# GRLV_double_30v_v0_3.net
KiCad netlist of a schematic drawn in Altium Designer
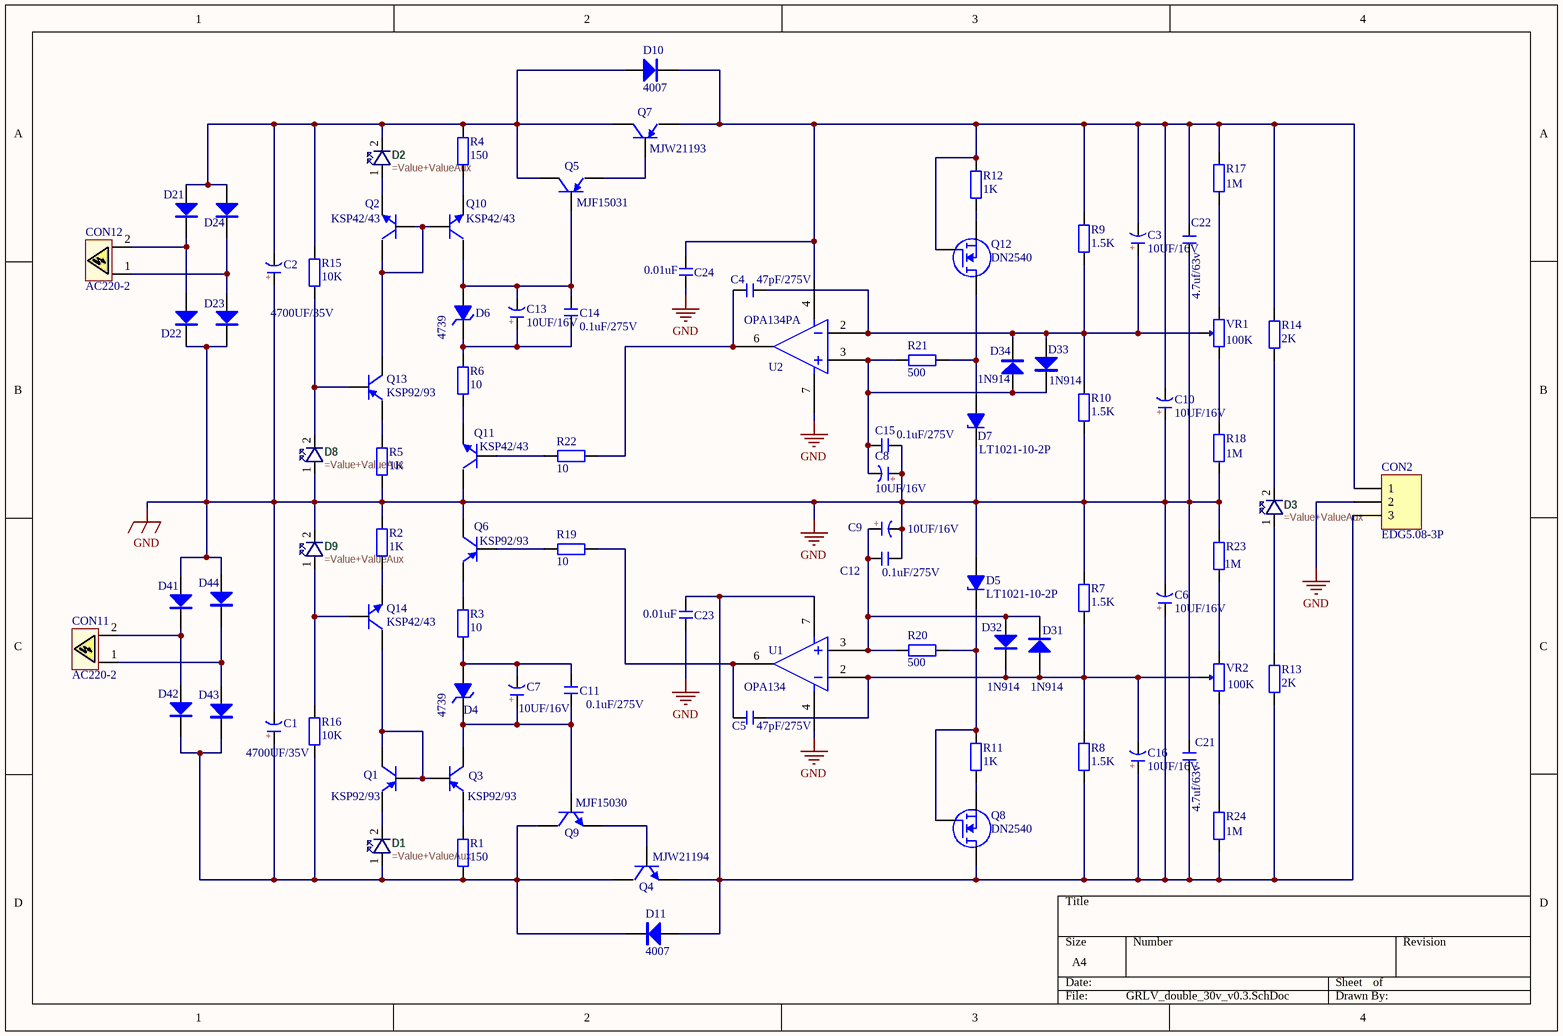
[diagram p0: GRLV_double_30v_v0.3.SchDoc]

(export (version "E")
  (design (tool "Eeschema 10.0.6"))
  (components
    (comp (ref "C1")
      (value "4700UF/35V")
      (footprint "CAP 10*22*31.5")
      (description "直插电解电容")
      (fields (field (name "版权归属") "源创客"))
      (libsource (lib "电阻-电容-电感") (part "C-CAP"))
    )
    (comp (ref "C2")
      (value "4700UF/35V")
      (footprint "CAP 10*22*31.5")
      (description "直插电解电容")
      (fields (field (name "版权归属") "源创客"))
      (libsource (lib "电阻-电容-电感") (part "C-CAP"))
    )
    (comp (ref "C3")
      (value "10UF/16V")
      (footprint "CAP 2.5*6.3*7")
      (description "直插电解电容")
      (fields (field (name "版权归属") "源创客"))
      (libsource (lib "电阻-电容-电感") (part "C-CAP"))
    )
    (comp (ref "C4")
      (value "47pF/275V")
      (footprint "CBB 6.3*6.3*5")
      (description "CBB电容")
      (fields (field (name "版权归属") "源创客"))
      (libsource (lib "电阻-电容-电感") (part "C-CBB"))
    )
    (comp (ref "C5")
      (value "47pF/275V")
      (footprint "CBB 6.3*6.3*5")
      (description "CBB电容")
      (fields (field (name "版权归属") "源创客"))
      (libsource (lib "电阻-电容-电感") (part "C-CBB"))
    )
    (comp (ref "C6")
      (value "10UF/16V")
      (footprint "CAP 3.5*8*11.5")
      (description "直插电解电容")
      (fields (field (name "版权归属") "源创客"))
      (libsource (lib "电阻-电容-电感") (part "C-CAP"))
    )
    (comp (ref "C7")
      (value "10UF/16V")
      (footprint "CAP 2.5*6.3*11.2")
      (description "直插电解电容")
      (fields (field (name "版权归属") "源创客"))
      (libsource (lib "电阻-电容-电感") (part "C-CAP"))
    )
    (comp (ref "C8")
      (value "10UF/16V")
      (footprint "CAP 2.5*6.3*7")
      (description "直插电解电容")
      (fields (field (name "版权归属") "源创客"))
      (libsource (lib "") (part "C-CAP_1"))
    )
    (comp (ref "C9")
      (value "10UF/16V")
      (footprint "CAP 2.5*6.3*7")
      (description "直插电解电容")
      (fields (field (name "版权归属") "源创客"))
      (libsource (lib "") (part "C-CAP_1"))
    )
    (comp (ref "C10")
      (value "10UF/16V")
      (footprint "CAP 3.5*8*11.5")
      (description "直插电解电容")
      (fields (field (name "版权归属") "源创客"))
      (libsource (lib "电阻-电容-电感") (part "C-CAP"))
    )
    (comp (ref "C11")
      (value "0.1uF/275V")
      (footprint "CBB 6.3*6.3*5")
      (description "CBB电容")
      (fields (field (name "版权归属") "源创客"))
      (libsource (lib "电阻-电容-电感") (part "C-CBB"))
    )
    (comp (ref "C12")
      (value "0.1uF/275V")
      (footprint "CBB 6.3*6.3*5")
      (description "CBB电容")
      (fields (field (name "版权归属") "源创客"))
      (libsource (lib "电阻-电容-电感") (part "C-CBB"))
    )
    (comp (ref "C13")
      (value "10UF/16V")
      (footprint "CAP 2.5*6.3*11.2")
      (description "直插电解电容")
      (fields (field (name "版权归属") "源创客"))
      (libsource (lib "电阻-电容-电感") (part "C-CAP"))
    )
    (comp (ref "C14")
      (value "0.1uF/275V")
      (footprint "CBB 6.3*6.3*5")
      (description "CBB电容")
      (fields (field (name "版权归属") "源创客"))
      (libsource (lib "电阻-电容-电感") (part "C-CBB"))
    )
    (comp (ref "C15")
      (value "0.1uF/275V")
      (footprint "CBB 6.3*6.3*5")
      (description "CBB电容")
      (fields (field (name "版权归属") "源创客"))
      (libsource (lib "电阻-电容-电感") (part "C-CBB"))
    )
    (comp (ref "C16")
      (value "10UF/16V")
      (footprint "CAP 2.5*6.3*7")
      (description "直插电解电容")
      (fields (field (name "版权归属") "源创客"))
      (libsource (lib "电阻-电容-电感") (part "C-CAP"))
    )
    (comp (ref "C21")
      (value "4.7uf/63v")
      (footprint "CBB 7.2*7.2*13")
      (description "MKS薄膜电容")
      (libsource (lib "电阻-电容-电感") (part "C-MKS"))
    )
    (comp (ref "C22")
      (value "4.7uf/63v")
      (footprint "CBB 7.2*7.2*13")
      (description "MKS薄膜电容")
      (libsource (lib "电阻-电容-电感") (part "C-MKS"))
    )
    (comp (ref "C23")
      (value "0.01uF")
      (footprint "CBB 6.3*6.3*5")
      (description "CBB电容")
      (fields (field (name "Comment") "0.01uF/275V") (field (name "版权归属") "源创客"))
      (libsource (lib "电阻-电容-电感") (part "C-CBB"))
    )
    (comp (ref "C24")
      (value "0.01uF")
      (footprint "CBB 6.3*6.3*5")
      (description "CBB电容")
      (fields (field (name "Comment") "0.01uF/275V") (field (name "版权归属") "源创客"))
      (libsource (lib "电阻-电容-电感") (part "C-CBB"))
    )
    (comp (ref "CON2")
      (value "EDG5.08-3P")
      (footprint "HX5.08-3S")
      (libsource (lib "Connectors") (part "EDG5.08-3P"))
    )
    (comp (ref "CON11")
      (value "AC220-2")
      (footprint "HX5.08-2L")
      (libsource (lib "Connectors") (part "AC220-2"))
    )
    (comp (ref "CON12")
      (value "AC220-2")
      (footprint "HX5.08-2L")
      (libsource (lib "Connectors") (part "AC220-2"))
    )
    (comp (ref "D1")
      (value "~")
      (footprint "LED 3MM-R")
      (description "直插式LED")
      (libsource (lib "LED") (part "LED"))
    )
    (comp (ref "D2")
      (value "~")
      (footprint "LED 3MM-R")
      (description "直插式LED")
      (libsource (lib "LED") (part "LED"))
    )
    (comp (ref "D3")
      (value "~")
      (footprint "LED 3MM-R")
      (description "直插式LED")
      (libsource (lib "LED") (part "LED"))
    )
    (comp (ref "D4")
      (value "4739")
      (footprint "DO-41")
      (description "9.1V/1W稳压管")
      (libsource (lib "二极管-整流桥") (part "1N4739"))
    )
    (comp (ref "D5")
      (value "LT1021-10-2P")
      (footprint "DIP8-300_MH")
      (description "10V Precision Reference 2 Pin Config")
      (libsource (lib "电压参考") (part "LT1021-10-2P"))
    )
    (comp (ref "D6")
      (value "4739")
      (footprint "DO-41")
      (description "9.1V/1W稳压管")
      (libsource (lib "二极管-整流桥") (part "1N4739"))
    )
    (comp (ref "D7")
      (value "LT1021-10-2P")
      (footprint "DIP8-300_MH")
      (description "10V Precision Reference 2 Pin Config")
      (libsource (lib "电压参考") (part "LT1021-10-2P"))
    )
    (comp (ref "D8")
      (value "~")
      (footprint "LED 3MM-R")
      (description "直插式LED")
      (libsource (lib "LED") (part "LED"))
    )
    (comp (ref "D9")
      (value "~")
      (footprint "LED 3MM-R")
      (description "直插式LED")
      (libsource (lib "LED") (part "LED"))
    )
    (comp (ref "D10")
      (value "4007")
      (footprint "DO-41")
      (description "整流二极管")
      (fields (field (name "版权归属") "源创客"))
      (libsource (lib "二极管-整流桥") (part "1N4007"))
    )
    (comp (ref "D11")
      (value "4007")
      (footprint "DO-41")
      (description "整流二极管")
      (fields (field (name "版权归属") "源创客"))
      (libsource (lib "二极管-整流桥") (part "1N4007"))
    )
    (comp (ref "D21")
      (value "VS-HFA08TB60-M3")
      (footprint "TO220AC")
      (description "Ultrafast Soft Recovery Diado 8A 600V")
      (libsource (lib "二极管-整流桥") (part "VS-HFA08TB60-M3"))
    )
    (comp (ref "D22")
      (value "VS-HFA08TB60-M3")
      (footprint "TO220AC")
      (description "Ultrafast Soft Recovery Diado 8A 600V")
      (libsource (lib "二极管-整流桥") (part "VS-HFA08TB60-M3"))
    )
    (comp (ref "D23")
      (value "VS-HFA08TB60-M3")
      (footprint "TO220AC")
      (description "Ultrafast Soft Recovery Diado 8A 600V")
      (libsource (lib "二极管-整流桥") (part "VS-HFA08TB60-M3"))
    )
    (comp (ref "D24")
      (value "VS-HFA08TB60-M3")
      (footprint "TO220AC")
      (description "Ultrafast Soft Recovery Diado 8A 600V")
      (libsource (lib "二极管-整流桥") (part "VS-HFA08TB60-M3"))
    )
    (comp (ref "D31")
      (value "1N914")
      (footprint "DO-35")
      (description "高速开关管 1V/0.25W")
      (libsource (lib "二极管-整流桥") (part "1N914"))
    )
    (comp (ref "D32")
      (value "1N914")
      (footprint "DO-35")
      (description "高速开关管 1V/0.25W")
      (libsource (lib "二极管-整流桥") (part "1N914"))
    )
    (comp (ref "D33")
      (value "1N914")
      (footprint "DO-35")
      (description "高速开关管 1V/0.25W")
      (libsource (lib "二极管-整流桥") (part "1N914"))
    )
    (comp (ref "D34")
      (value "1N914")
      (footprint "DO-35")
      (description "高速开关管 1V/0.25W")
      (libsource (lib "二极管-整流桥") (part "1N914"))
    )
    (comp (ref "D41")
      (value "VS-HFA08TB60-M3")
      (footprint "TO220AC")
      (description "Ultrafast Soft Recovery Diado 8A 600V")
      (libsource (lib "二极管-整流桥") (part "VS-HFA08TB60-M3"))
    )
    (comp (ref "D42")
      (value "VS-HFA08TB60-M3")
      (footprint "TO220AC")
      (description "Ultrafast Soft Recovery Diado 8A 600V")
      (libsource (lib "二极管-整流桥") (part "VS-HFA08TB60-M3"))
    )
    (comp (ref "D43")
      (value "VS-HFA08TB60-M3")
      (footprint "TO220AC")
      (description "Ultrafast Soft Recovery Diado 8A 600V")
      (libsource (lib "二极管-整流桥") (part "VS-HFA08TB60-M3"))
    )
    (comp (ref "D44")
      (value "VS-HFA08TB60-M3")
      (footprint "TO220AC")
      (description "Ultrafast Soft Recovery Diado 8A 600V")
      (libsource (lib "二极管-整流桥") (part "VS-HFA08TB60-M3"))
    )
    (comp (ref "Q1")
      (value "KSP92/93")
      (footprint "TO92A")
      (description "High Voltage PNP Transistor")
      (libsource (lib "三极管") (part "KSP92/93"))
    )
    (comp (ref "Q2")
      (value "KSP42/43")
      (footprint "TO92A")
      (description "High Voltage NPN Transistor")
      (libsource (lib "三极管") (part "KSP42/43"))
    )
    (comp (ref "Q3")
      (value "KSP92/93")
      (footprint "TO92A")
      (description "High Voltage PNP Transistor")
      (libsource (lib "三极管") (part "KSP92/93"))
    )
    (comp (ref "Q4")
      (value "MJW21194")
      (footprint "TO247V")
      (description "Power NPN Transistor")
      (libsource (lib "三极管") (part "MJW21194"))
    )
    (comp (ref "Q5")
      (value "MJF15031")
      (footprint "TO220V")
      (description "Power PNP Transistor")
      (libsource (lib "三极管") (part "MJF15031"))
    )
    (comp (ref "Q6")
      (value "KSP92/93")
      (footprint "TO92A")
      (description "High Voltage PNP Transistor")
      (libsource (lib "三极管") (part "KSP92/93"))
    )
    (comp (ref "Q7")
      (value "MJW21193")
      (footprint "TO247V")
      (description "Power PNP Transistor")
      (libsource (lib "三极管") (part "MJW21193"))
    )
    (comp (ref "Q8")
      (value "DN2540")
      (footprint "TO92A")
      (description "N沟道耗尽型DMOS场效应管 400V/150ma")
      (libsource (lib "场效应管") (part "DN2540"))
    )
    (comp (ref "Q9")
      (value "MJF15030")
      (footprint "TO220V")
      (description "Power NPN Transistor")
      (libsource (lib "三极管") (part "MJF15030"))
    )
    (comp (ref "Q10")
      (value "KSP42/43")
      (footprint "TO92A")
      (description "High Voltage NPN Transistor")
      (libsource (lib "三极管") (part "KSP42/43"))
    )
    (comp (ref "Q11")
      (value "KSP42/43")
      (footprint "TO92A")
      (description "High Voltage NPN Transistor")
      (libsource (lib "三极管") (part "KSP42/43"))
    )
    (comp (ref "Q12")
      (value "DN2540")
      (footprint "TO92A")
      (description "N沟道耗尽型DMOS场效应管 400V/150ma")
      (libsource (lib "场效应管") (part "DN2540"))
    )
    (comp (ref "Q13")
      (value "KSP92/93")
      (footprint "TO92A")
      (description "High Voltage PNP Transistor")
      (libsource (lib "三极管") (part "KSP92/93"))
    )
    (comp (ref "Q14")
      (value "KSP42/43")
      (footprint "TO92A")
      (description "High Voltage NPN Transistor")
      (libsource (lib "三极管") (part "KSP42/43"))
    )
    (comp (ref "R1")
      (value "150")
      (footprint "RS 1/4W")
      (description "直插色环电阻")
      (fields (field (name "版权归属") "源创客"))
      (libsource (lib "电阻-电容-电感") (part "R-CRR"))
    )
    (comp (ref "R2")
      (value "1K")
      (footprint "RS 1/4W")
      (description "直插色环电阻")
      (fields (field (name "版权归属") "源创客"))
      (libsource (lib "电阻-电容-电感") (part "R-CRR"))
    )
    (comp (ref "R3")
      (value "10")
      (footprint "RS 1/4W")
      (description "直插色环电阻")
      (fields (field (name "版权归属") "源创客"))
      (libsource (lib "电阻-电容-电感") (part "R-CRR"))
    )
    (comp (ref "R4")
      (value "150")
      (footprint "RS 1/4W")
      (description "直插色环电阻")
      (fields (field (name "版权归属") "源创客"))
      (libsource (lib "电阻-电容-电感") (part "R-CRR"))
    )
    (comp (ref "R5")
      (value "1K")
      (footprint "RS 1/4W")
      (description "直插色环电阻")
      (fields (field (name "版权归属") "源创客"))
      (libsource (lib "电阻-电容-电感") (part "R-CRR"))
    )
    (comp (ref "R6")
      (value "10")
      (footprint "RS 1/4W")
      (description "直插色环电阻")
      (fields (field (name "版权归属") "源创客"))
      (libsource (lib "电阻-电容-电感") (part "R-CRR"))
    )
    (comp (ref "R7")
      (value "1.5K")
      (footprint "RS 1/4W")
      (description "直插色环电阻")
      (fields (field (name "版权归属") "源创客"))
      (libsource (lib "电阻-电容-电感") (part "R-CRR"))
    )
    (comp (ref "R8")
      (value "1.5K")
      (footprint "RS 1/4W")
      (description "直插色环电阻")
      (fields (field (name "版权归属") "源创客"))
      (libsource (lib "电阻-电容-电感") (part "R-CRR"))
    )
    (comp (ref "R9")
      (value "1.5K")
      (footprint "RS 1/4W")
      (description "直插色环电阻")
      (fields (field (name "版权归属") "源创客"))
      (libsource (lib "电阻-电容-电感") (part "R-CRR"))
    )
    (comp (ref "R10")
      (value "1.5K")
      (footprint "RS 1/4W")
      (description "直插色环电阻")
      (fields (field (name "版权归属") "源创客"))
      (libsource (lib "电阻-电容-电感") (part "R-CRR"))
    )
    (comp (ref "R11")
      (value "1K")
      (footprint "RS 1/4W")
      (description "直插色环电阻")
      (fields (field (name "版权归属") "源创客"))
      (libsource (lib "电阻-电容-电感") (part "R-CRR"))
    )
    (comp (ref "R12")
      (value "1K")
      (footprint "RS 1/4W")
      (description "直插色环电阻")
      (fields (field (name "版权归属") "源创客"))
      (libsource (lib "电阻-电容-电感") (part "R-CRR"))
    )
    (comp (ref "R13")
      (value "2K")
      (footprint "RS 1/4W")
      (description "直插色环电阻")
      (fields (field (name "版权归属") "源创客"))
      (libsource (lib "电阻-电容-电感") (part "R-CRR"))
    )
    (comp (ref "R14")
      (value "2K")
      (footprint "RS 1/4W")
      (description "直插色环电阻")
      (fields (field (name "版权归属") "源创客"))
      (libsource (lib "电阻-电容-电感") (part "R-CRR"))
    )
    (comp (ref "R15")
      (value "10K")
      (footprint "RS 1/4W")
      (description "直插色环电阻")
      (fields (field (name "版权归属") "源创客"))
      (libsource (lib "电阻-电容-电感") (part "R-CRR"))
    )
    (comp (ref "R16")
      (value "10K")
      (footprint "RS 1/4W")
      (description "直插色环电阻")
      (fields (field (name "版权归属") "源创客"))
      (libsource (lib "电阻-电容-电感") (part "R-CRR"))
    )
    (comp (ref "R17")
      (value "1M")
      (footprint "RS 1/4W")
      (description "直插色环电阻")
      (fields (field (name "版权归属") "源创客"))
      (libsource (lib "电阻-电容-电感") (part "R-CRR"))
    )
    (comp (ref "R18")
      (value "1M")
      (footprint "RS 1/4W")
      (description "直插色环电阻")
      (fields (field (name "版权归属") "源创客"))
      (libsource (lib "电阻-电容-电感") (part "R-CRR"))
    )
    (comp (ref "R19")
      (value "10")
      (footprint "RS 1/4W")
      (description "直插色环电阻")
      (fields (field (name "版权归属") "源创客"))
      (libsource (lib "电阻-电容-电感") (part "R-CRR"))
    )
    (comp (ref "R20")
      (value "500")
      (footprint "RS 1/4W")
      (description "直插色环电阻")
      (fields (field (name "版权归属") "源创客"))
      (libsource (lib "电阻-电容-电感") (part "R-CRR"))
    )
    (comp (ref "R21")
      (value "500")
      (footprint "RS 1/4W")
      (description "直插色环电阻")
      (fields (field (name "版权归属") "源创客"))
      (libsource (lib "电阻-电容-电感") (part "R-CRR"))
    )
    (comp (ref "R22")
      (value "10")
      (footprint "RS 1/4W")
      (description "直插色环电阻")
      (fields (field (name "版权归属") "源创客"))
      (libsource (lib "电阻-电容-电感") (part "R-CRR"))
    )
    (comp (ref "R23")
      (value "1M")
      (footprint "RS 1/4W")
      (description "直插色环电阻")
      (fields (field (name "版权归属") "源创客"))
      (libsource (lib "电阻-电容-电感") (part "R-CRR"))
    )
    (comp (ref "R24")
      (value "1M")
      (footprint "RS 1/4W")
      (description "直插色环电阻")
      (fields (field (name "版权归属") "源创客"))
      (libsource (lib "电阻-电容-电感") (part "R-CRR"))
    )
    (comp (ref "U1") (value "OPA134") (footprint "DIP8-300_MH") (libsource (lib "运放") (part "OPA134PA")))
    (comp (ref "U2") (value "OPA134PA") (footprint "DIP8-300_MH") (libsource (lib "运放") (part "OPA134PA")))
    (comp (ref "VR1")
      (value "100K")
      (footprint "RS 1/2W-VR")
      (description "直插可调电阻-顶调")
      (fields (field (name "Comment") "VR-W"))
      (libsource (lib "电阻-电容-电感") (part "VR-W"))
    )
    (comp (ref "VR2")
      (value "100K")
      (footprint "RS 1/2W-VR")
      (description "直插可调电阻-顶调")
      (fields (field (name "Comment") "VR-W"))
      (libsource (lib "电阻-电容-电感") (part "VR-W"))
    )
  )
  (nets
    (net (code "1") (name "GND") (class "Default")
      (node (ref "C1") (pin "2") (pinfunction "K_2") (pintype "passive"))
      (node (ref "C10") (pin "1") (pinfunction "A_1") (pintype "passive"))
      (node (ref "C12") (pin "2") (pinfunction "2_2") (pintype "passive"))
      (node (ref "C15") (pin "2") (pinfunction "2_2") (pintype "passive"))
      (node (ref "C2") (pin "1") (pinfunction "A_1") (pintype "passive"))
      (node (ref "C21") (pin "2") (pinfunction "2_2") (pintype "passive"))
      (node (ref "C22") (pin "1") (pinfunction "1_1") (pintype "passive"))
      (node (ref "C23") (pin "1") (pinfunction "1_1") (pintype "passive"))
      (node (ref "C24") (pin "1") (pinfunction "1_1") (pintype "passive"))
      (node (ref "C6") (pin "2") (pinfunction "K_2") (pintype "passive"))
      (node (ref "C8") (pin "1") (pinfunction "A_1") (pintype "passive"))
      (node (ref "C9") (pin "2") (pinfunction "K_2") (pintype "passive"))
      (node (ref "CON2") (pin "2") (pinfunction "2_2") (pintype "passive"))
      (node (ref "D22") (pin "1") (pinfunction "Cathode_1") (pintype "passive"))
      (node (ref "D23") (pin "1") (pinfunction "Cathode_1") (pintype "passive"))
      (node (ref "D41") (pin "2") (pinfunction "Anode_2") (pintype "passive"))
      (node (ref "D44") (pin "2") (pinfunction "Anode_2") (pintype "passive"))
      (node (ref "D5") (pin "4") (pinfunction "A_4") (pintype "passive"))
      (node (ref "D7") (pin "6") (pinfunction "K_6") (pintype "passive"))
      (node (ref "D8") (pin "1") (pinfunction "A_1") (pintype "passive"))
      (node (ref "D9") (pin "2") (pinfunction "K_2") (pintype "passive"))
      (node (ref "Q11") (pin "3") (pinfunction "C_3") (pintype "passive"))
      (node (ref "Q6") (pin "3") (pinfunction "C_3") (pintype "passive"))
      (node (ref "R10") (pin "1") (pinfunction "1_1") (pintype "passive"))
      (node (ref "R18") (pin "1") (pinfunction "1_1") (pintype "passive"))
      (node (ref "R2") (pin "2") (pinfunction "2_2") (pintype "passive"))
      (node (ref "R23") (pin "2") (pinfunction "2_2") (pintype "passive"))
      (node (ref "R5") (pin "1") (pinfunction "1_1") (pintype "passive"))
      (node (ref "R7") (pin "2") (pinfunction "2_2") (pintype "passive"))
      (node (ref "U1") (pin "4") (pinfunction "V-_4") (pintype "passive"))
      (node (ref "U2") (pin "7") (pinfunction "V+_7") (pintype "passive"))
    )
    (net (code "2") (name "Net-(C1-A)") (class "Default")
      (node (ref "C1") (pin "1") (pinfunction "A_1") (pintype "passive"))
      (node (ref "D1") (pin "1") (pinfunction "A_1") (pintype "passive"))
      (node (ref "D11") (pin "2") (pinfunction "K_2") (pintype "passive"))
      (node (ref "D42") (pin "1") (pinfunction "Cathode_1") (pintype "passive"))
      (node (ref "D43") (pin "1") (pinfunction "Cathode_1") (pintype "passive"))
      (node (ref "Q4") (pin "2") (pinfunction "C_2") (pintype "passive"))
      (node (ref "Q9") (pin "2") (pinfunction "C_2") (pintype "passive"))
      (node (ref "R1") (pin "1") (pinfunction "1_1") (pintype "passive"))
      (node (ref "R16") (pin "1") (pinfunction "1_1") (pintype "passive"))
    )
    (net (code "3") (name "Net-(C2-K)") (class "Default")
      (node (ref "C2") (pin "2") (pinfunction "K_2") (pintype "passive"))
      (node (ref "D10") (pin "1") (pinfunction "A_1") (pintype "passive"))
      (node (ref "D2") (pin "2") (pinfunction "K_2") (pintype "passive"))
      (node (ref "D21") (pin "2") (pinfunction "Anode_2") (pintype "passive"))
      (node (ref "D24") (pin "2") (pinfunction "Anode_2") (pintype "passive"))
      (node (ref "Q5") (pin "2") (pinfunction "C_2") (pintype "passive"))
      (node (ref "Q7") (pin "2") (pinfunction "C_2") (pintype "passive"))
      (node (ref "R15") (pin "2") (pinfunction "2_2") (pintype "passive"))
      (node (ref "R4") (pin "2") (pinfunction "2_2") (pintype "passive"))
    )
    (net (code "4") (name "Net-(C3-A)") (class "Default")
      (node (ref "C3") (pin "1") (pinfunction "A_1") (pintype "passive"))
      (node (ref "C4") (pin "2") (pinfunction "2_2") (pintype "passive"))
      (node (ref "D33") (pin "1") (pinfunction "A_1") (pintype "passive"))
      (node (ref "D34") (pin "2") (pinfunction "K_2") (pintype "passive"))
      (node (ref "R10") (pin "2") (pinfunction "2_2") (pintype "passive"))
      (node (ref "R9") (pin "1") (pinfunction "1_1") (pintype "passive"))
      (node (ref "U2") (pin "2") (pinfunction "-in_2") (pintype "passive"))
      (node (ref "VR1") (pin "3") (pinfunction "3_3") (pintype "passive"))
    )
    (net (code "5") (name "Net-(C7-A)") (class "Default")
      (node (ref "C11") (pin "1") (pinfunction "1_1") (pintype "passive"))
      (node (ref "C7") (pin "1") (pinfunction "A_1") (pintype "passive"))
      (node (ref "D4") (pin "2") (pinfunction "K_2") (pintype "passive"))
      (node (ref "Q3") (pin "3") (pinfunction "C_3") (pintype "passive"))
      (node (ref "Q9") (pin "1") (pinfunction "B_1") (pintype "passive"))
    )
    (net (code "6") (name "Net-(C7-K)") (class "Default")
      (node (ref "C11") (pin "2") (pinfunction "2_2") (pintype "passive"))
      (node (ref "C7") (pin "2") (pinfunction "K_2") (pintype "passive"))
      (node (ref "D4") (pin "1") (pinfunction "A_1") (pintype "passive"))
      (node (ref "R3") (pin "1") (pinfunction "1_1") (pintype "passive"))
    )
    (net (code "7") (name "Net-(C8-K)") (class "Default")
      (node (ref "C15") (pin "1") (pinfunction "1_1") (pintype "passive"))
      (node (ref "C8") (pin "2") (pinfunction "K_2") (pintype "passive"))
      (node (ref "D33") (pin "2") (pinfunction "K_2") (pintype "passive"))
      (node (ref "D34") (pin "1") (pinfunction "A_1") (pintype "passive"))
      (node (ref "R21") (pin "1") (pinfunction "1_1") (pintype "passive"))
      (node (ref "U2") (pin "3") (pinfunction "+in_3") (pintype "passive"))
    )
    (net (code "8") (name "Net-(C9-A)") (class "Default")
      (node (ref "C12") (pin "1") (pinfunction "1_1") (pintype "passive"))
      (node (ref "C9") (pin "1") (pinfunction "A_1") (pintype "passive"))
      (node (ref "D31") (pin "2") (pinfunction "K_2") (pintype "passive"))
      (node (ref "D32") (pin "1") (pinfunction "A_1") (pintype "passive"))
      (node (ref "R20") (pin "1") (pinfunction "1_1") (pintype "passive"))
      (node (ref "U1") (pin "3") (pinfunction "+in_3") (pintype "passive"))
    )
    (net (code "9") (name "Net-(C10-K)") (class "Default")
      (node (ref "C10") (pin "2") (pinfunction "K_2") (pintype "passive"))
      (node (ref "C22") (pin "2") (pinfunction "2_2") (pintype "passive"))
      (node (ref "C24") (pin "2") (pinfunction "2_2") (pintype "passive"))
      (node (ref "C3") (pin "2") (pinfunction "K_2") (pintype "passive"))
      (node (ref "CON2") (pin "1") (pinfunction "1_1") (pintype "passive"))
      (node (ref "D10") (pin "2") (pinfunction "K_2") (pintype "passive"))
      (node (ref "Q12") (pin "2") (pinfunction "G_2") (pintype "passive"))
      (node (ref "Q7") (pin "3") (pinfunction "E_3") (pintype "passive"))
      (node (ref "R12") (pin "2") (pinfunction "2_2") (pintype "passive"))
      (node (ref "R14") (pin "2") (pinfunction "2_2") (pintype "passive"))
      (node (ref "R17") (pin "2") (pinfunction "2_2") (pintype "passive"))
      (node (ref "R9") (pin "2") (pinfunction "2_2") (pintype "passive"))
      (node (ref "U2") (pin "4") (pinfunction "V-_4") (pintype "passive"))
    )
    (net (code "10") (name "Net-(C13-A)") (class "Default")
      (node (ref "C13") (pin "1") (pinfunction "A_1") (pintype "passive"))
      (node (ref "C14") (pin "1") (pinfunction "1_1") (pintype "passive"))
      (node (ref "D6") (pin "2") (pinfunction "K_2") (pintype "passive"))
      (node (ref "R6") (pin "2") (pinfunction "2_2") (pintype "passive"))
    )
    (net (code "11") (name "Net-(C13-K)") (class "Default")
      (node (ref "C13") (pin "2") (pinfunction "K_2") (pintype "passive"))
      (node (ref "C14") (pin "2") (pinfunction "2_2") (pintype "passive"))
      (node (ref "D6") (pin "1") (pinfunction "A_1") (pintype "passive"))
      (node (ref "Q10") (pin "3") (pinfunction "C_3") (pintype "passive"))
      (node (ref "Q5") (pin "1") (pinfunction "B_1") (pintype "passive"))
    )
    (net (code "12") (name "Net-(C16-A)") (class "Default")
      (node (ref "C16") (pin "1") (pinfunction "A_1") (pintype "passive"))
      (node (ref "C21") (pin "1") (pinfunction "1_1") (pintype "passive"))
      (node (ref "C23") (pin "2") (pinfunction "2_2") (pintype "passive"))
      (node (ref "C6") (pin "1") (pinfunction "A_1") (pintype "passive"))
      (node (ref "CON2") (pin "3") (pinfunction "3_3") (pintype "passive"))
      (node (ref "D11") (pin "1") (pinfunction "A_1") (pintype "passive"))
      (node (ref "Q4") (pin "3") (pinfunction "E_3") (pintype "passive"))
      (node (ref "Q8") (pin "3") (pinfunction "D_3") (pintype "passive"))
      (node (ref "R13") (pin "2") (pinfunction "2_2") (pintype "passive"))
      (node (ref "R24") (pin "1") (pinfunction "1_1") (pintype "passive"))
      (node (ref "R8") (pin "1") (pinfunction "1_1") (pintype "passive"))
      (node (ref "U1") (pin "7") (pinfunction "V+_7") (pintype "passive"))
    )
    (net (code "13") (name "Net-(C16-K)") (class "Default")
      (node (ref "C16") (pin "2") (pinfunction "K_2") (pintype "passive"))
      (node (ref "C5") (pin "2") (pinfunction "2_2") (pintype "passive"))
      (node (ref "D31") (pin "1") (pinfunction "A_1") (pintype "passive"))
      (node (ref "D32") (pin "2") (pinfunction "K_2") (pintype "passive"))
      (node (ref "R7") (pin "1") (pinfunction "1_1") (pintype "passive"))
      (node (ref "R8") (pin "2") (pinfunction "2_2") (pintype "passive"))
      (node (ref "U1") (pin "2") (pinfunction "-in_2") (pintype "passive"))
      (node (ref "VR2") (pin "3") (pinfunction "3_3") (pintype "passive"))
    )
    (net (code "14") (name "Net-(CON11-G)") (class "Default")
      (node (ref "CON11") (pin "2") (pinfunction "G_2") (pintype "passive"))
      (node (ref "D41") (pin "1") (pinfunction "Cathode_1") (pintype "passive"))
      (node (ref "D42") (pin "2") (pinfunction "Anode_2") (pintype "passive"))
    )
    (net (code "15") (name "Net-(CON11-L)") (class "Default")
      (node (ref "CON11") (pin "1") (pinfunction "L_1") (pintype "passive"))
      (node (ref "D43") (pin "2") (pinfunction "Anode_2") (pintype "passive"))
      (node (ref "D44") (pin "1") (pinfunction "Cathode_1") (pintype "passive"))
    )
    (net (code "16") (name "Net-(CON12-G)") (class "Default")
      (node (ref "CON12") (pin "2") (pinfunction "G_2") (pintype "passive"))
      (node (ref "D21") (pin "1") (pinfunction "Cathode_1") (pintype "passive"))
      (node (ref "D22") (pin "2") (pinfunction "Anode_2") (pintype "passive"))
    )
    (net (code "17") (name "Net-(CON12-L)") (class "Default")
      (node (ref "CON12") (pin "1") (pinfunction "L_1") (pintype "passive"))
      (node (ref "D23") (pin "2") (pinfunction "Anode_2") (pintype "passive"))
      (node (ref "D24") (pin "1") (pinfunction "Cathode_1") (pintype "passive"))
    )
    (net (code "18") (name "Net-(D1-K)") (class "Default")
      (node (ref "D1") (pin "2") (pinfunction "K_2") (pintype "passive"))
      (node (ref "Q1") (pin "1") (pinfunction "E_1") (pintype "passive"))
    )
    (net (code "19") (name "Net-(D2-A)") (class "Default")
      (node (ref "D2") (pin "1") (pinfunction "A_1") (pintype "passive"))
      (node (ref "Q2") (pin "1") (pinfunction "E_1") (pintype "passive"))
    )
    (net (code "20") (name "Net-(D3-A)") (class "Default")
      (node (ref "D3") (pin "1") (pinfunction "A_1") (pintype "passive"))
      (node (ref "R13") (pin "1") (pinfunction "1_1") (pintype "passive"))
    )
    (net (code "21") (name "Net-(D3-K)") (class "Default")
      (node (ref "D3") (pin "2") (pinfunction "K_2") (pintype "passive"))
      (node (ref "R14") (pin "1") (pinfunction "1_1") (pintype "passive"))
    )
    (net (code "22") (name "Net-(D5-K)") (class "Default")
      (node (ref "D5") (pin "6") (pinfunction "K_6") (pintype "passive"))
      (node (ref "Q8") (pin "2") (pinfunction "G_2") (pintype "passive"))
      (node (ref "R11") (pin "2") (pinfunction "2_2") (pintype "passive"))
      (node (ref "R20") (pin "2") (pinfunction "2_2") (pintype "passive"))
    )
    (net (code "23") (name "Net-(D7-A)") (class "Default")
      (node (ref "D7") (pin "4") (pinfunction "A_4") (pintype "passive"))
      (node (ref "Q12") (pin "3") (pinfunction "D_3") (pintype "passive"))
      (node (ref "R21") (pin "2") (pinfunction "2_2") (pintype "passive"))
    )
    (net (code "24") (name "Net-(D8-K)") (class "Default")
      (node (ref "D8") (pin "2") (pinfunction "K_2") (pintype "passive"))
      (node (ref "Q13") (pin "2") (pinfunction "B_2") (pintype "passive"))
      (node (ref "R15") (pin "1") (pinfunction "1_1") (pintype "passive"))
    )
    (net (code "25") (name "Net-(D9-A)") (class "Default")
      (node (ref "D9") (pin "1") (pinfunction "A_1") (pintype "passive"))
      (node (ref "Q14") (pin "2") (pinfunction "B_2") (pintype "passive"))
      (node (ref "R16") (pin "2") (pinfunction "2_2") (pintype "passive"))
    )
    (net (code "26") (name "Net-(Q1-B)") (class "Default")
      (node (ref "Q1") (pin "2") (pinfunction "B_2") (pintype "passive"))
      (node (ref "Q1") (pin "3") (pinfunction "C_3") (pintype "passive"))
      (node (ref "Q14") (pin "3") (pinfunction "C_3") (pintype "passive"))
      (node (ref "Q3") (pin "2") (pinfunction "B_2") (pintype "passive"))
    )
    (net (code "27") (name "Net-(Q3-E)") (class "Default")
      (node (ref "Q3") (pin "1") (pinfunction "E_1") (pintype "passive"))
      (node (ref "R1") (pin "2") (pinfunction "2_2") (pintype "passive"))
    )
    (net (code "28") (name "Net-(Q4-B)") (class "Default")
      (node (ref "Q4") (pin "1") (pinfunction "B_1") (pintype "passive"))
      (node (ref "Q9") (pin "3") (pinfunction "E_3") (pintype "passive"))
    )
    (net (code "29") (name "Net-(Q5-E)") (class "Default")
      (node (ref "Q5") (pin "3") (pinfunction "E_3") (pintype "passive"))
      (node (ref "Q7") (pin "1") (pinfunction "B_1") (pintype "passive"))
    )
    (net (code "30") (name "Net-(Q6-B)") (class "Default")
      (node (ref "Q6") (pin "2") (pinfunction "B_2") (pintype "passive"))
      (node (ref "R19") (pin "1") (pinfunction "1_1") (pintype "passive"))
    )
    (net (code "31") (name "Net-(Q6-E)") (class "Default")
      (node (ref "Q6") (pin "1") (pinfunction "E_1") (pintype "passive"))
      (node (ref "R3") (pin "2") (pinfunction "2_2") (pintype "passive"))
    )
    (net (code "32") (name "Net-(Q8-S)") (class "Default")
      (node (ref "Q8") (pin "1") (pinfunction "S_1") (pintype "passive"))
      (node (ref "R11") (pin "1") (pinfunction "1_1") (pintype "passive"))
    )
    (net (code "33") (name "Net-(Q10-B)") (class "Default")
      (node (ref "Q10") (pin "2") (pinfunction "B_2") (pintype "passive"))
      (node (ref "Q13") (pin "3") (pinfunction "C_3") (pintype "passive"))
      (node (ref "Q2") (pin "2") (pinfunction "B_2") (pintype "passive"))
      (node (ref "Q2") (pin "3") (pinfunction "C_3") (pintype "passive"))
    )
    (net (code "34") (name "Net-(Q10-E)") (class "Default")
      (node (ref "Q10") (pin "1") (pinfunction "E_1") (pintype "passive"))
      (node (ref "R4") (pin "1") (pinfunction "1_1") (pintype "passive"))
    )
    (net (code "35") (name "Net-(Q11-B)") (class "Default")
      (node (ref "Q11") (pin "2") (pinfunction "B_2") (pintype "passive"))
      (node (ref "R22") (pin "1") (pinfunction "1_1") (pintype "passive"))
    )
    (net (code "36") (name "Net-(Q11-E)") (class "Default")
      (node (ref "Q11") (pin "1") (pinfunction "E_1") (pintype "passive"))
      (node (ref "R6") (pin "1") (pinfunction "1_1") (pintype "passive"))
    )
    (net (code "37") (name "Net-(Q12-S)") (class "Default")
      (node (ref "Q12") (pin "1") (pinfunction "S_1") (pintype "passive"))
      (node (ref "R12") (pin "1") (pinfunction "1_1") (pintype "passive"))
    )
    (net (code "38") (name "Net-(Q13-E)") (class "Default")
      (node (ref "Q13") (pin "1") (pinfunction "E_1") (pintype "passive"))
      (node (ref "R5") (pin "2") (pinfunction "2_2") (pintype "passive"))
    )
    (net (code "39") (name "Net-(Q14-E)") (class "Default")
      (node (ref "Q14") (pin "1") (pinfunction "E_1") (pintype "passive"))
      (node (ref "R2") (pin "1") (pinfunction "1_1") (pintype "passive"))
    )
    (net (code "40") (name "Net-(R17-Pad1)") (class "Default")
      (node (ref "R17") (pin "1") (pinfunction "1_1") (pintype "passive"))
      (node (ref "VR1") (pin "2") (pinfunction "2_2") (pintype "passive"))
    )
    (net (code "41") (name "Net-(R18-Pad2)") (class "Default")
      (node (ref "R18") (pin "2") (pinfunction "2_2") (pintype "passive"))
      (node (ref "VR1") (pin "1") (pinfunction "1_1") (pintype "passive"))
    )
    (net (code "42") (name "Net-(R23-Pad1)") (class "Default")
      (node (ref "R23") (pin "1") (pinfunction "1_1") (pintype "passive"))
      (node (ref "VR2") (pin "2") (pinfunction "2_2") (pintype "passive"))
    )
    (net (code "43") (name "Net-(R24-Pad2)") (class "Default")
      (node (ref "R24") (pin "2") (pinfunction "2_2") (pintype "passive"))
      (node (ref "VR2") (pin "1") (pinfunction "1_1") (pintype "passive"))
    )
    (net (code "44") (name "Net-(U1-out)") (class "Default")
      (node (ref "C5") (pin "1") (pinfunction "1_1") (pintype "passive"))
      (node (ref "R19") (pin "2") (pinfunction "2_2") (pintype "passive"))
      (node (ref "U1") (pin "6") (pinfunction "out_6") (pintype "passive"))
    )
    (net (code "45") (name "Net-(U2-out)") (class "Default")
      (node (ref "C4") (pin "1") (pinfunction "1_1") (pintype "passive"))
      (node (ref "R22") (pin "2") (pinfunction "2_2") (pintype "passive"))
      (node (ref "U2") (pin "6") (pinfunction "out_6") (pintype "passive"))
    )
  )
)
